# arduinoboard_v1.net
KiCad netlist of a schematic drawn in EAGLE
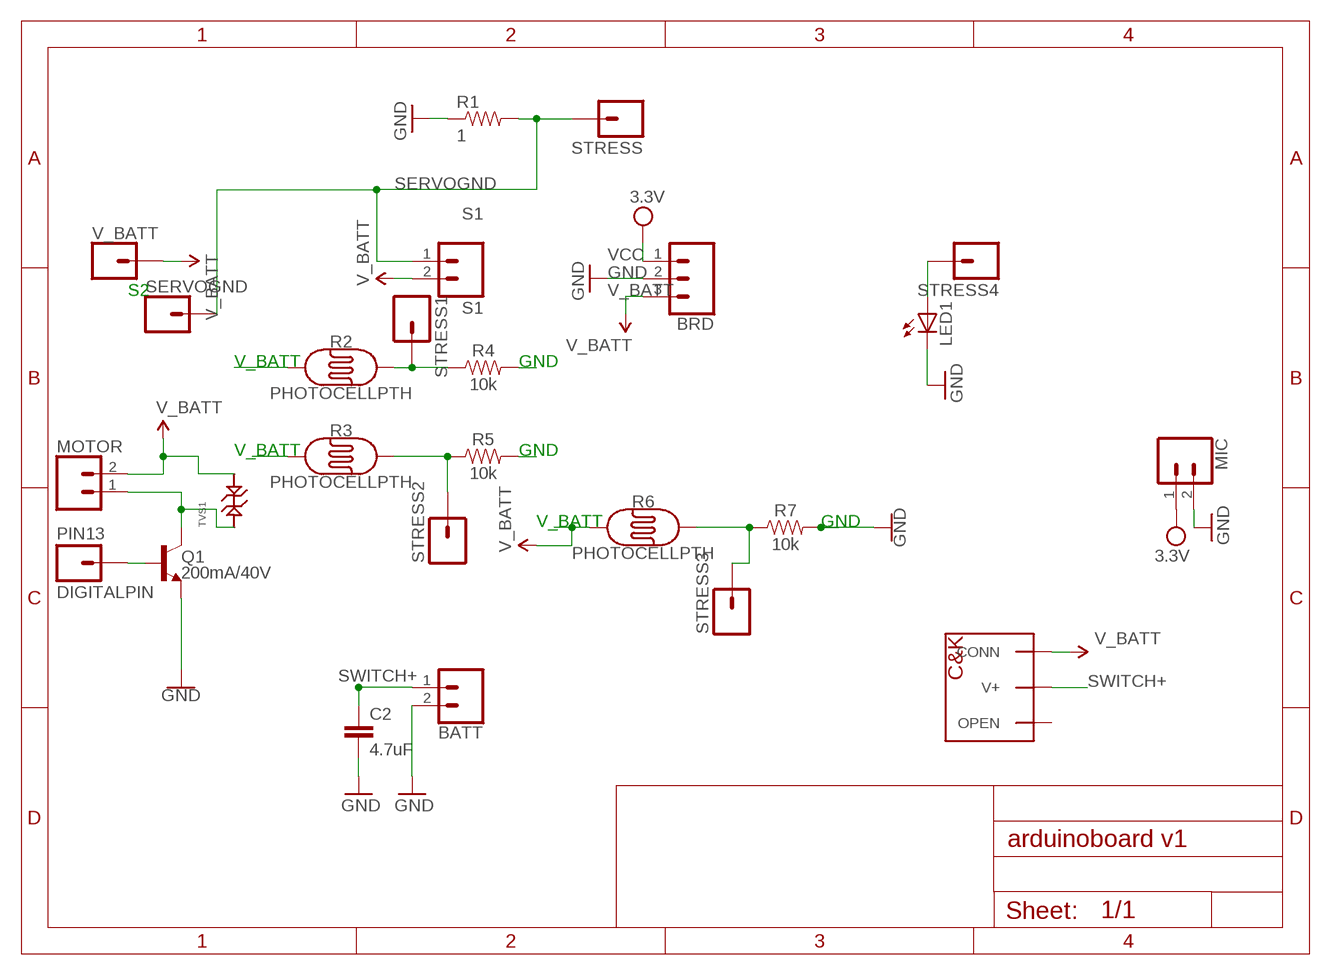
[diagram p0: schematic, sheet 1]

(export (version "E")
  (design (tool "Eeschema 10.0.6"))
  (components
    (comp (ref "BATT")
      (value "CONN_02")
      (footprint "eagle-import:1X02")
      (libsource (lib "eagle-import") (part "CONN_02"))
    )
    (comp (ref "BRD")
      (value "CONN_03")
      (footprint "eagle-import:1X03")
      (libsource (lib "eagle-import") (part "CONN_03"))
    )
    (comp (ref "C2")
      (value "4.7uF")
      (footprint "eagle-import:0603-CAP")
      (libsource (lib "eagle-import") (part "4.7UF-6.3V-10%(0603)0603"))
    )
    (comp (ref "LED1")
      (value "LEDCHIPLED_1206")
      (footprint "eagle-import:CHIPLED_1206")
      (libsource (lib "eagle-import") (part "LEDCHIPLED_1206"))
    )
    (comp (ref "MIC")
      (value "CONN_02")
      (footprint "eagle-import:1X02")
      (libsource (lib "eagle-import") (part "CONN_02"))
    )
    (comp (ref "MOTOR")
      (value "CONN_02")
      (footprint "eagle-import:1X02")
      (libsource (lib "eagle-import") (part "CONN_02"))
    )
    (comp (ref "PIN13")
      (value "DIGITALPIN")
      (footprint "eagle-import:1X01")
      (libsource (lib "eagle-import") (part "M01PTH"))
    )
    (comp (ref "Q1")
      (value "200mA/40V")
      (footprint "eagle-import:TO-92")
      (libsource (lib "eagle-import") (part "TRANS_NPN-2N3904"))
    )
    (comp (ref "R1")
      (value "1")
      (footprint "eagle-import:0603-RES")
      (libsource (lib "eagle-import") (part "2.0KOHM1/10W5%(0603)"))
    )
    (comp (ref "R2")
      (value "PHOTOCELLPTH")
      (footprint "eagle-import:PHOTOCELL")
      (libsource (lib "eagle-import") (part "PHOTOCELLPTH"))
    )
    (comp (ref "R3")
      (value "PHOTOCELLPTH")
      (footprint "eagle-import:PHOTOCELL")
      (libsource (lib "eagle-import") (part "PHOTOCELLPTH"))
    )
    (comp (ref "R4")
      (value "10k")
      (footprint "eagle-import:0603")
      (libsource (lib "eagle-import") (part "10KOHM-0603-1/10W-1%"))
    )
    (comp (ref "R5")
      (value "10k")
      (footprint "eagle-import:0603")
      (libsource (lib "eagle-import") (part "10KOHM-0603-1/10W-1%"))
    )
    (comp (ref "R6")
      (value "PHOTOCELLPTH")
      (footprint "eagle-import:PHOTOCELL")
      (libsource (lib "eagle-import") (part "PHOTOCELLPTH"))
    )
    (comp (ref "R7")
      (value "10k")
      (footprint "eagle-import:0603")
      (libsource (lib "eagle-import") (part "10KOHM-0603-1/10W-1%"))
    )
    (comp (ref "S1")
      (value "S1")
      (footprint "eagle-import:1X02")
      (libsource (lib "eagle-import") (part "CONN_02"))
    )
    (comp (ref "SERVOGND")
      (value "CONN_01")
      (footprint "eagle-import:1X01")
      (libsource (lib "eagle-import") (part "CONN_01"))
    )
    (comp (ref "STRESS")
      (value "M01PTH")
      (footprint "eagle-import:1X01")
      (libsource (lib "eagle-import") (part "M01PTH"))
    )
    (comp (ref "STRESS1")
      (value "M01PTH")
      (footprint "eagle-import:1X01")
      (libsource (lib "eagle-import") (part "M01PTH"))
    )
    (comp (ref "STRESS2")
      (value "M01PTH")
      (footprint "eagle-import:1X01")
      (libsource (lib "eagle-import") (part "M01PTH"))
    )
    (comp (ref "STRESS3")
      (value "M01PTH")
      (footprint "eagle-import:1X01")
      (libsource (lib "eagle-import") (part "M01PTH"))
    )
    (comp (ref "STRESS4")
      (value "M01PTH")
      (footprint "eagle-import:1X01")
      (libsource (lib "eagle-import") (part "M01PTH"))
    )
    (comp (ref "TVS1")
      (value "TVS_DIODE_SOD-923")
      (footprint "eagle-import:SOD-923")
      (libsource (lib "eagle-import") (part "TVS_DIODE_SOD-923"))
    )
    (comp (ref "U$1")
      (value "WILL-BLACKSLIDESWITCH")
      (footprint "eagle-import:WILL-BLACKSLIDESWITCH")
      (libsource (lib "eagle-import") (part "WILL-BLACKSLIDESWITCH"))
    )
    (comp (ref "V_BATT")
      (value "CONN_01")
      (footprint "eagle-import:1X01")
      (libsource (lib "eagle-import") (part "CONN_01"))
    )
  )
  (nets
    (net (code "1") (name "/SERVOGND") (class "Default")
      (node (ref "R1") (pin "2") (pinfunction "2_2") (pintype "passive"))
      (node (ref "S1") (pin "1") (pinfunction "1_1") (pintype "passive"))
      (node (ref "SERVOGND") (pin "1") (pinfunction "1_1") (pintype "passive"))
      (node (ref "STRESS") (pin "1") (pinfunction "1_1") (pintype "passive"))
    )
    (net (code "2") (name "/SWITCH+") (class "Default")
      (node (ref "BATT") (pin "1") (pinfunction "1_1") (pintype "passive"))
      (node (ref "C2") (pin "1") (pinfunction "1_1") (pintype "passive"))
      (node (ref "U$1") (pin "V+") (pinfunction "V+_V+") (pintype "bidirectional"))
    )
    (net (code "3") (name "3.3V") (class "Default")
      (node (ref "BRD") (pin "1") (pinfunction "1_1") (pintype "passive"))
      (node (ref "MIC") (pin "1") (pinfunction "1_1") (pintype "passive"))
    )
    (net (code "4") (name "GND") (class "Default")
      (node (ref "BATT") (pin "2") (pinfunction "2_2") (pintype "passive"))
      (node (ref "BRD") (pin "2") (pinfunction "2_2") (pintype "passive"))
      (node (ref "C2") (pin "2") (pinfunction "2_2") (pintype "passive"))
      (node (ref "LED1") (pin "C") (pinfunction "C_C") (pintype "passive"))
      (node (ref "MIC") (pin "2") (pinfunction "2_2") (pintype "passive"))
      (node (ref "Q1") (pin "1") (pinfunction "E_1") (pintype "passive"))
      (node (ref "R1") (pin "1") (pinfunction "1_1") (pintype "passive"))
      (node (ref "R4") (pin "2") (pinfunction "2_2") (pintype "passive"))
      (node (ref "R5") (pin "2") (pinfunction "2_2") (pintype "passive"))
      (node (ref "R7") (pin "2") (pinfunction "2_2") (pintype "passive"))
    )
    (net (code "5") (name "Net-(LED1-PadA)") (class "Default")
      (node (ref "LED1") (pin "A") (pinfunction "A_A") (pintype "passive"))
      (node (ref "STRESS4") (pin "1") (pinfunction "1_1") (pintype "passive"))
    )
    (net (code "6") (name "Net-(Q1-B)") (class "Default")
      (node (ref "PIN13") (pin "1") (pinfunction "1_1") (pintype "passive"))
      (node (ref "Q1") (pin "2") (pinfunction "B_2") (pintype "passive"))
    )
    (net (code "7") (name "Net-(Q1-C)") (class "Default")
      (node (ref "MOTOR") (pin "1") (pinfunction "1_1") (pintype "passive"))
      (node (ref "Q1") (pin "3") (pinfunction "C_3") (pintype "passive"))
      (node (ref "TVS1") (pin "P$1") (pinfunction "P$1_P$1") (pintype "bidirectional"))
    )
    (net (code "8") (name "Net-(R2-P$2)") (class "Default")
      (node (ref "R2") (pin "2") (pinfunction "P$2_2") (pintype "bidirectional"))
      (node (ref "R4") (pin "1") (pinfunction "1_1") (pintype "passive"))
      (node (ref "STRESS1") (pin "1") (pinfunction "1_1") (pintype "passive"))
    )
    (net (code "9") (name "Net-(R3-P$2)") (class "Default")
      (node (ref "R3") (pin "2") (pinfunction "P$2_2") (pintype "bidirectional"))
      (node (ref "R5") (pin "1") (pinfunction "1_1") (pintype "passive"))
      (node (ref "STRESS2") (pin "1") (pinfunction "1_1") (pintype "passive"))
    )
    (net (code "10") (name "Net-(R6-P$2)") (class "Default")
      (node (ref "R6") (pin "2") (pinfunction "P$2_2") (pintype "bidirectional"))
      (node (ref "R7") (pin "1") (pinfunction "1_1") (pintype "passive"))
      (node (ref "STRESS3") (pin "1") (pinfunction "1_1") (pintype "passive"))
    )
    (net (code "11") (name "V_BATT") (class "Default")
      (node (ref "BRD") (pin "3") (pinfunction "3_3") (pintype "passive"))
      (node (ref "MOTOR") (pin "2") (pinfunction "2_2") (pintype "passive"))
      (node (ref "R2") (pin "1") (pinfunction "P$1_1") (pintype "bidirectional"))
      (node (ref "R3") (pin "1") (pinfunction "P$1_1") (pintype "bidirectional"))
      (node (ref "R6") (pin "1") (pinfunction "P$1_1") (pintype "bidirectional"))
      (node (ref "S1") (pin "2") (pinfunction "2_2") (pintype "passive"))
      (node (ref "TVS1") (pin "P$2") (pinfunction "P$2_P$2") (pintype "bidirectional"))
      (node (ref "U$1") (pin "CONN") (pinfunction "CONN_CONN") (pintype "bidirectional"))
      (node (ref "V_BATT") (pin "1") (pinfunction "1_1") (pintype "passive"))
    )
    (net (code "12") (name "unconnected-(U$1-OPEN-PadNC)") (class "Default")
      (node (ref "U$1") (pin "NC") (pinfunction "OPEN_NC") (pintype "bidirectional"))
    )
  )
)
